# MCU.net
KiCad netlist of a schematic drawn in Altium Designer
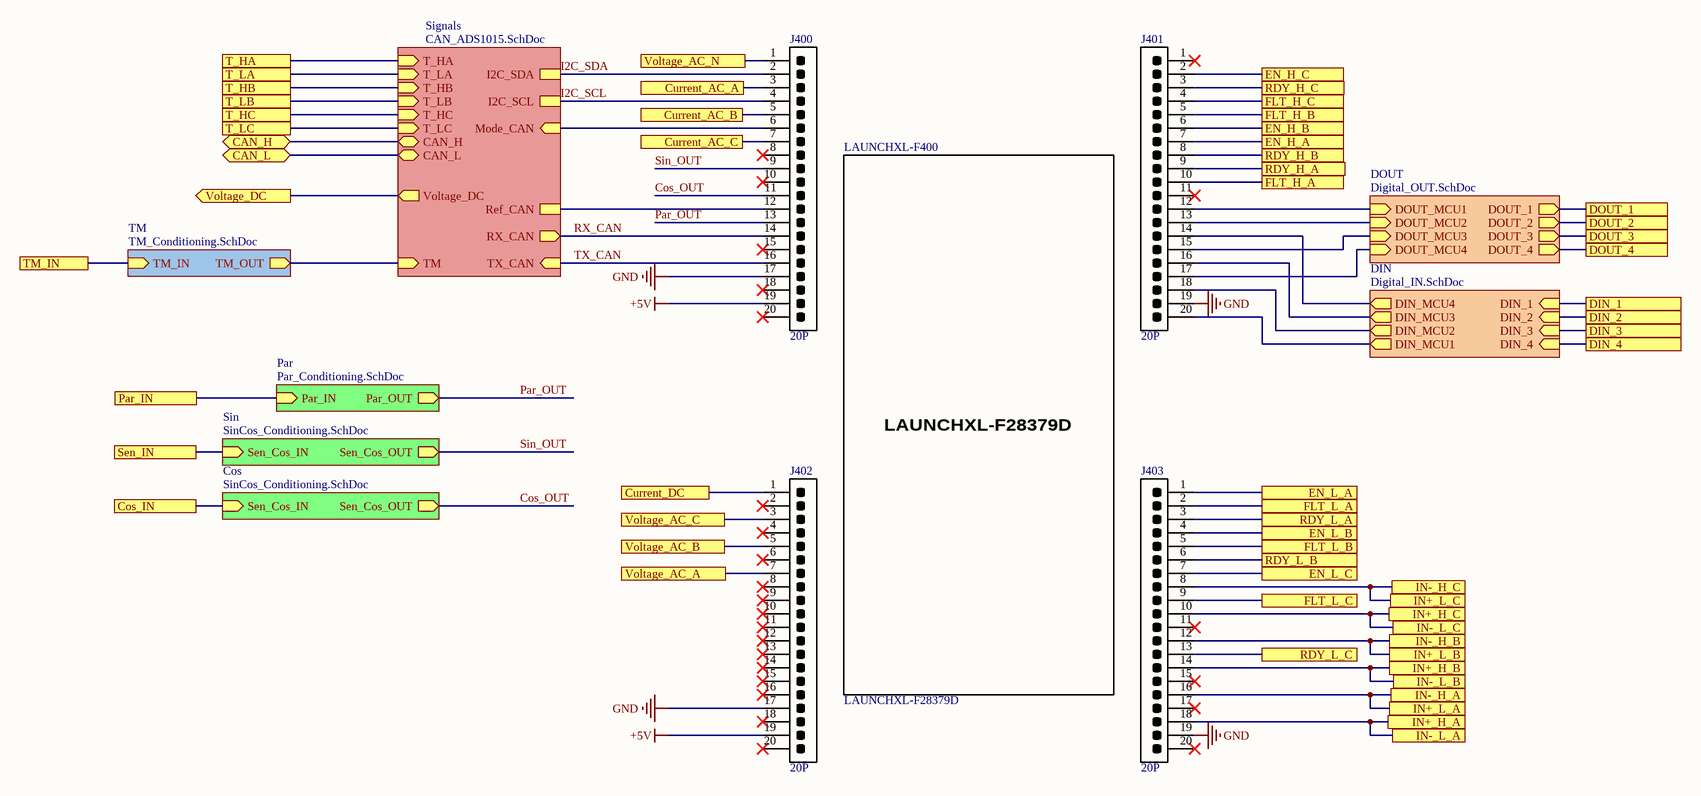
[diagram p0: MCU.SchDoc]

(export (version "E")
  (design (tool "Eeschema 10.0.6"))
  (components
    (comp (ref "J400")
      (value "20P")
      (footprint "PIN_HEADER_THT_20P")
      (description "Alojamientos de cables y cabecera 2.54mm Male Header, 2X20pin, Straight, PA6T, Gold Flash")
      (fields (field (name "MPN") "SSK03-MPH-254-B10") (field (name "MANUFACTURER") "Same Sky"))
      (libsource (lib "eUSR_Database") (part "CONN 20P"))
    )
    (comp (ref "J401")
      (value "20P")
      (footprint "PIN_HEADER_THT_20P")
      (description "Alojamientos de cables y cabecera 2.54mm Male Header, 2X20pin, Straight, PA6T, Gold Flash")
      (fields (field (name "MPN") "SSK03-MPH-254-B10") (field (name "MANUFACTURER") "Same Sky"))
      (libsource (lib "") (part "CONN 20P_1"))
    )
    (comp (ref "J402")
      (value "20P")
      (footprint "PIN_HEADER_THT_20P")
      (description "Alojamientos de cables y cabecera 2.54mm Male Header, 2X20pin, Straight, PA6T, Gold Flash")
      (fields (field (name "MPN") "SSK03-MPH-254-B10") (field (name "MANUFACTURER") "Same Sky"))
      (libsource (lib "eUSR_Database") (part "CONN 20P"))
    )
    (comp (ref "J403")
      (value "20P")
      (footprint "PIN_HEADER_THT_20P")
      (description "Alojamientos de cables y cabecera 2.54mm Male Header, 2X20pin, Straight, PA6T, Gold Flash")
      (fields (field (name "MPN") "SSK03-MPH-254-B10") (field (name "MANUFACTURER") "Same Sky"))
      (libsource (lib "") (part "CONN 20P_1"))
    )
    (comp (ref "LAUNCHXL-F400")
      (value "LAUNCHXL-F28379D")
      (footprint "LAUNCHXL-F28379D")
      (description "Equipos y placas de desarrollo - TMS320 C2000 F28379D DELFIN O LAUNCHPAD")
      (fields (field (name "MANUFACTURER") "Texas Instruments"))
      (libsource (lib "eUSR_Database") (part "LAUNCHXL-F28379D"))
    )
  )
  (nets
    (net (code "1") (name "+5V") (class "Default")
      (node (ref "J400") (pin "19") (pinfunction "19_19") (pintype "passive"))
      (node (ref "J402") (pin "19") (pinfunction "19_19") (pintype "passive"))
    )
    (net (code "5") (name "/Cos_OUT") (class "Default")
      (node (ref "J400") (pin "11") (pinfunction "11_11") (pintype "passive"))
    )
    (net (code "6") (name "/Current_AC_A") (class "Default")
      (node (ref "J400") (pin "3") (pinfunction "3_3") (pintype "passive"))
    )
    (net (code "7") (name "/Current_AC_B") (class "Default")
      (node (ref "J400") (pin "5") (pinfunction "5_5") (pintype "passive"))
    )
    (net (code "8") (name "/Current_AC_C") (class "Default")
      (node (ref "J400") (pin "7") (pinfunction "7_7") (pintype "passive"))
    )
    (net (code "9") (name "/Current_DC") (class "Default")
      (node (ref "J402") (pin "1") (pinfunction "1_1") (pintype "passive"))
    )
    (net (code "14") (name "/DIN_MCU1") (class "Default")
      (node (ref "J401") (pin "20") (pinfunction "20_20") (pintype "passive"))
    )
    (net (code "15") (name "/DIN_MCU2") (class "Default")
      (node (ref "J401") (pin "18") (pinfunction "18_18") (pintype "passive"))
    )
    (net (code "16") (name "/DIN_MCU3") (class "Default")
      (node (ref "J401") (pin "16") (pinfunction "16_16") (pintype "passive"))
    )
    (net (code "17") (name "/DIN_MCU4") (class "Default")
      (node (ref "J401") (pin "14") (pinfunction "14_14") (pintype "passive"))
    )
    (net (code "22") (name "/DOUT_MCU1") (class "Default")
      (node (ref "J401") (pin "12") (pinfunction "12_12") (pintype "passive"))
    )
    (net (code "23") (name "/DOUT_MCU2") (class "Default")
      (node (ref "J401") (pin "13") (pinfunction "13_13") (pintype "passive"))
    )
    (net (code "24") (name "/DOUT_MCU3") (class "Default")
      (node (ref "J401") (pin "15") (pinfunction "15_15") (pintype "passive"))
    )
    (net (code "25") (name "/DOUT_MCU4") (class "Default")
      (node (ref "J401") (pin "17") (pinfunction "17_17") (pintype "passive"))
    )
    (net (code "26") (name "/EN_H_A") (class "Default")
      (node (ref "J401") (pin "7") (pinfunction "7_7") (pintype "passive"))
    )
    (net (code "27") (name "/EN_H_B") (class "Default")
      (node (ref "J401") (pin "6") (pinfunction "6_6") (pintype "passive"))
    )
    (net (code "28") (name "/EN_H_C") (class "Default")
      (node (ref "J401") (pin "2") (pinfunction "2_2") (pintype "passive"))
    )
    (net (code "29") (name "/EN_L_A") (class "Default")
      (node (ref "J403") (pin "1") (pinfunction "1_1") (pintype "passive"))
    )
    (net (code "30") (name "/EN_L_B") (class "Default")
      (node (ref "J403") (pin "4") (pinfunction "4_4") (pintype "passive"))
    )
    (net (code "31") (name "/EN_L_C") (class "Default")
      (node (ref "J403") (pin "7") (pinfunction "7_7") (pintype "passive"))
    )
    (net (code "32") (name "/FLT_H_A") (class "Default")
      (node (ref "J401") (pin "10") (pinfunction "10_10") (pintype "passive"))
    )
    (net (code "33") (name "/FLT_H_B") (class "Default")
      (node (ref "J401") (pin "5") (pinfunction "5_5") (pintype "passive"))
    )
    (net (code "34") (name "/FLT_H_C") (class "Default")
      (node (ref "J401") (pin "4") (pinfunction "4_4") (pintype "passive"))
    )
    (net (code "35") (name "/FLT_L_A") (class "Default")
      (node (ref "J403") (pin "2") (pinfunction "2_2") (pintype "passive"))
    )
    (net (code "36") (name "/FLT_L_B") (class "Default")
      (node (ref "J403") (pin "5") (pinfunction "5_5") (pintype "passive"))
    )
    (net (code "37") (name "/FLT_L_C") (class "Default")
      (node (ref "J403") (pin "9") (pinfunction "9_9") (pintype "passive"))
    )
    (net (code "38") (name "/I2C_SCL") (class "Default")
      (node (ref "J400") (pin "4") (pinfunction "4_4") (pintype "passive"))
    )
    (net (code "39") (name "/I2C_SDA") (class "Default")
      (node (ref "J400") (pin "2") (pinfunction "2_2") (pintype "passive"))
    )
    (net (code "40") (name "/IN+_H_A") (class "Default")
      (node (ref "J403") (pin "18") (pinfunction "18_18") (pintype "passive"))
    )
    (net (code "41") (name "/IN+_H_B") (class "Default")
      (node (ref "J403") (pin "14") (pinfunction "14_14") (pintype "passive"))
    )
    (net (code "42") (name "/IN+_H_C") (class "Default")
      (node (ref "J403") (pin "10") (pinfunction "10_10") (pintype "passive"))
    )
    (net (code "43") (name "/IN+_L_A") (class "Default")
      (node (ref "J403") (pin "16") (pinfunction "16_16") (pintype "passive"))
    )
    (net (code "44") (name "/IN+_L_B") (class "Default")
      (node (ref "J403") (pin "12") (pinfunction "12_12") (pintype "passive"))
    )
    (net (code "45") (name "/IN+_L_C") (class "Default")
      (node (ref "J403") (pin "8") (pinfunction "8_8") (pintype "passive"))
    )
    (net (code "46") (name "/Mode_CAN") (class "Default")
      (node (ref "J400") (pin "6") (pinfunction "6_6") (pintype "passive"))
    )
    (net (code "48") (name "/Par_OUT") (class "Default")
      (node (ref "J400") (pin "13") (pinfunction "13_13") (pintype "passive"))
    )
    (net (code "49") (name "/RDY_H_A") (class "Default")
      (node (ref "J401") (pin "9") (pinfunction "9_9") (pintype "passive"))
    )
    (net (code "50") (name "/RDY_H_B") (class "Default")
      (node (ref "J401") (pin "8") (pinfunction "8_8") (pintype "passive"))
    )
    (net (code "51") (name "/RDY_H_C") (class "Default")
      (node (ref "J401") (pin "3") (pinfunction "3_3") (pintype "passive"))
    )
    (net (code "52") (name "/RDY_L_A") (class "Default")
      (node (ref "J403") (pin "3") (pinfunction "3_3") (pintype "passive"))
    )
    (net (code "53") (name "/RDY_L_B") (class "Default")
      (node (ref "J403") (pin "6") (pinfunction "6_6") (pintype "passive"))
    )
    (net (code "54") (name "/RDY_L_C") (class "Default")
      (node (ref "J403") (pin "13") (pinfunction "13_13") (pintype "passive"))
    )
    (net (code "55") (name "/RX_CAN") (class "Default")
      (node (ref "J400") (pin "14") (pinfunction "14_14") (pintype "passive"))
    )
    (net (code "56") (name "/Ref_CAN") (class "Default")
      (node (ref "J400") (pin "12") (pinfunction "12_12") (pintype "passive"))
    )
    (net (code "58") (name "/Sin_OUT") (class "Default")
      (node (ref "J400") (pin "9") (pinfunction "9_9") (pintype "passive"))
    )
    (net (code "61") (name "/TX_CAN") (class "Default")
      (node (ref "J400") (pin "16") (pinfunction "16_16") (pintype "passive"))
    )
    (net (code "68") (name "/Voltage_AC_A") (class "Default")
      (node (ref "J402") (pin "7") (pinfunction "7_7") (pintype "passive"))
    )
    (net (code "69") (name "/Voltage_AC_B") (class "Default")
      (node (ref "J402") (pin "5") (pinfunction "5_5") (pintype "passive"))
    )
    (net (code "70") (name "/Voltage_AC_C") (class "Default")
      (node (ref "J402") (pin "3") (pinfunction "3_3") (pintype "passive"))
    )
    (net (code "71") (name "/Voltage_AC_N") (class "Default")
      (node (ref "J400") (pin "1") (pinfunction "1_1") (pintype "passive"))
    )
    (net (code "73") (name "GND") (class "Default")
      (node (ref "J400") (pin "17") (pinfunction "17_17") (pintype "passive"))
      (node (ref "J401") (pin "19") (pinfunction "19_19") (pintype "passive"))
      (node (ref "J402") (pin "17") (pinfunction "17_17") (pintype "passive"))
      (node (ref "J403") (pin "19") (pinfunction "19_19") (pintype "passive"))
    )
    (net (code "74") (name "unconnected-(J400-Pad8)") (class "Default")
      (node (ref "J400") (pin "8") (pinfunction "8_8") (pintype "passive+no_connect"))
    )
    (net (code "75") (name "unconnected-(J400-Pad10)") (class "Default")
      (node (ref "J400") (pin "10") (pinfunction "10_10") (pintype "passive+no_connect"))
    )
    (net (code "76") (name "unconnected-(J400-Pad15)") (class "Default")
      (node (ref "J400") (pin "15") (pinfunction "15_15") (pintype "passive+no_connect"))
    )
    (net (code "77") (name "unconnected-(J400-Pad18)") (class "Default")
      (node (ref "J400") (pin "18") (pinfunction "18_18") (pintype "passive+no_connect"))
    )
    (net (code "78") (name "unconnected-(J400-Pad20)") (class "Default")
      (node (ref "J400") (pin "20") (pinfunction "20_20") (pintype "passive+no_connect"))
    )
    (net (code "79") (name "unconnected-(J401-Pad1)") (class "Default")
      (node (ref "J401") (pin "1") (pinfunction "1_1") (pintype "passive+no_connect"))
    )
    (net (code "80") (name "unconnected-(J401-Pad11)") (class "Default")
      (node (ref "J401") (pin "11") (pinfunction "11_11") (pintype "passive+no_connect"))
    )
    (net (code "81") (name "unconnected-(J402-Pad2)") (class "Default")
      (node (ref "J402") (pin "2") (pinfunction "2_2") (pintype "passive+no_connect"))
    )
    (net (code "82") (name "unconnected-(J402-Pad4)") (class "Default")
      (node (ref "J402") (pin "4") (pinfunction "4_4") (pintype "passive+no_connect"))
    )
    (net (code "83") (name "unconnected-(J402-Pad6)") (class "Default")
      (node (ref "J402") (pin "6") (pinfunction "6_6") (pintype "passive+no_connect"))
    )
    (net (code "84") (name "unconnected-(J402-Pad8)") (class "Default")
      (node (ref "J402") (pin "8") (pinfunction "8_8") (pintype "passive+no_connect"))
    )
    (net (code "85") (name "unconnected-(J402-Pad9)") (class "Default")
      (node (ref "J402") (pin "9") (pinfunction "9_9") (pintype "passive+no_connect"))
    )
    (net (code "86") (name "unconnected-(J402-Pad10)") (class "Default")
      (node (ref "J402") (pin "10") (pinfunction "10_10") (pintype "passive+no_connect"))
    )
    (net (code "87") (name "unconnected-(J402-Pad11)") (class "Default")
      (node (ref "J402") (pin "11") (pinfunction "11_11") (pintype "passive+no_connect"))
    )
    (net (code "88") (name "unconnected-(J402-Pad12)") (class "Default")
      (node (ref "J402") (pin "12") (pinfunction "12_12") (pintype "passive+no_connect"))
    )
    (net (code "89") (name "unconnected-(J402-Pad13)") (class "Default")
      (node (ref "J402") (pin "13") (pinfunction "13_13") (pintype "passive+no_connect"))
    )
    (net (code "90") (name "unconnected-(J402-Pad14)") (class "Default")
      (node (ref "J402") (pin "14") (pinfunction "14_14") (pintype "passive+no_connect"))
    )
    (net (code "91") (name "unconnected-(J402-Pad15)") (class "Default")
      (node (ref "J402") (pin "15") (pinfunction "15_15") (pintype "passive+no_connect"))
    )
    (net (code "92") (name "unconnected-(J402-Pad16)") (class "Default")
      (node (ref "J402") (pin "16") (pinfunction "16_16") (pintype "passive+no_connect"))
    )
    (net (code "93") (name "unconnected-(J402-Pad18)") (class "Default")
      (node (ref "J402") (pin "18") (pinfunction "18_18") (pintype "passive+no_connect"))
    )
    (net (code "94") (name "unconnected-(J402-Pad20)") (class "Default")
      (node (ref "J402") (pin "20") (pinfunction "20_20") (pintype "passive+no_connect"))
    )
    (net (code "95") (name "unconnected-(J403-Pad11)") (class "Default")
      (node (ref "J403") (pin "11") (pinfunction "11_11") (pintype "passive+no_connect"))
    )
    (net (code "96") (name "unconnected-(J403-Pad15)") (class "Default")
      (node (ref "J403") (pin "15") (pinfunction "15_15") (pintype "passive+no_connect"))
    )
    (net (code "97") (name "unconnected-(J403-Pad17)") (class "Default")
      (node (ref "J403") (pin "17") (pinfunction "17_17") (pintype "passive+no_connect"))
    )
    (net (code "98") (name "unconnected-(J403-Pad20)") (class "Default")
      (node (ref "J403") (pin "20") (pinfunction "20_20") (pintype "passive+no_connect"))
    )
  )
)
